# ruka.net
KiCad netlist of a schematic drawn in Altium Designer
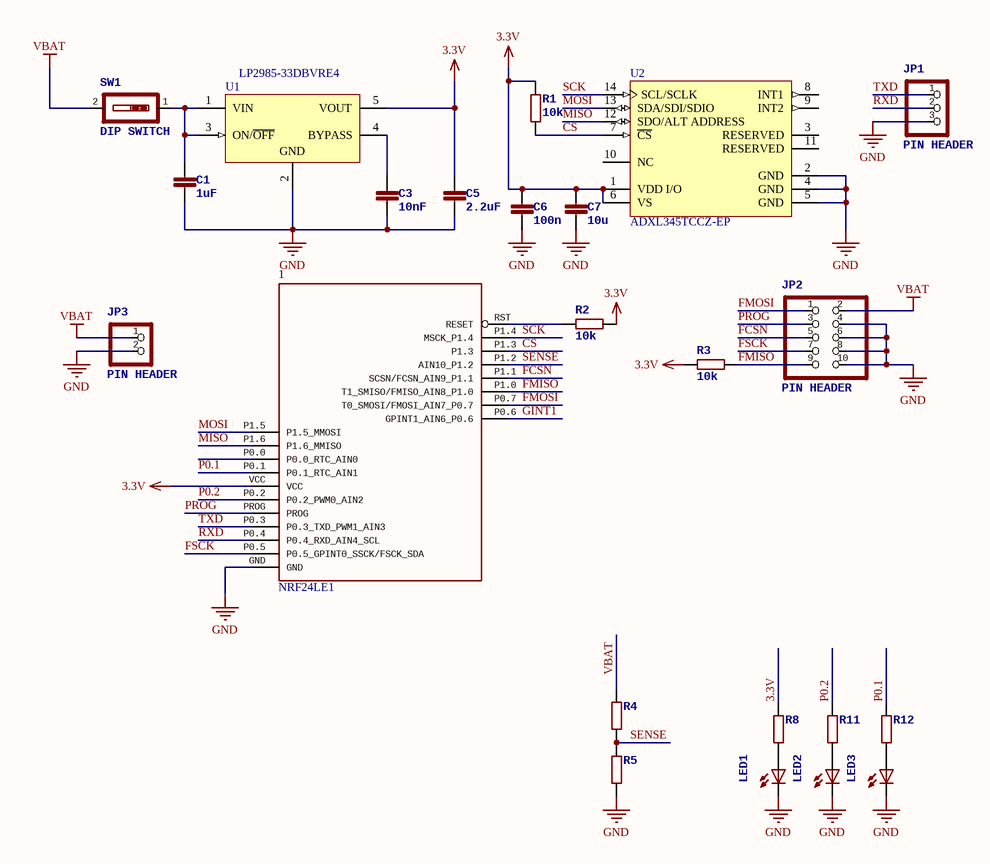
[diagram p0: ruka.SchDoc]

(export (version "E")
  (design (tool "Eeschema 10.0.6"))
  (components
    (comp (ref "1") (value "NRF24LE1") (footprint "SMDNRF") (libsource (lib "nrf24le1") (part "NRF24LE1")))
    (comp (ref "C1") (value "1uF") (footprint "C0805K") (libsource (lib "rcl") (part "C-EUC0805K")))
    (comp (ref "C3") (value "10nF") (footprint "C0805K") (libsource (lib "rcl") (part "C-EUC0805K")))
    (comp (ref "C5") (value "2.2uF") (footprint "C0805K") (libsource (lib "rcl") (part "C-EUC0805K")))
    (comp (ref "C6") (value "100n") (footprint "C0805K") (libsource (lib "rcl") (part "C-EUC0805K")))
    (comp (ref "C7") (value "10u") (footprint "C0805K") (libsource (lib "rcl") (part "C-EUC0805K")))
    (comp (ref "JP1")
      (value "PIN HEADER")
      (footprint "1X03/90")
      (libsource (lib "pinhead") (part "PINHD-1X3/90"))
    )
    (comp (ref "JP2")
      (value "PIN HEADER")
      (footprint "2X05/90")
      (libsource (lib "pinhead") (part "PINHD-2X5/90"))
    )
    (comp (ref "JP3")
      (value "PIN HEADER")
      (footprint "1X02/90")
      (libsource (lib "pinhead") (part "PINHD-1X2/90"))
    )
    (comp (ref "LED1")
      (value "LED   OSRAM: - CHIPLED LG R971, LG N971, LY N971, LG Q971, LY Q971, LO R971, LY R971 LH N974, LH R974 LS Q976, LO")
      (footprint "CHIP-LED0603")
      (libsource (lib "led") (part "LEDCHIP-LED0603"))
    )
    (comp (ref "LED2")
      (value "LED   OSRAM: - CHIPLED LG R971, LG N971, LY N971, LG Q971, LY Q971, LO R971, LY R971 LH N974, LH R974 LS Q976, LO")
      (footprint "CHIP-LED0603")
      (libsource (lib "led") (part "LEDCHIP-LED0603"))
    )
    (comp (ref "LED3")
      (value "LED   OSRAM: - CHIPLED LG R971, LG N971, LY N971, LG Q971, LY Q971, LO R971, LY R971 LH N974, LH R974 LS Q976, LO")
      (footprint "CHIP-LED0603")
      (libsource (lib "led") (part "LEDCHIP-LED0603"))
    )
    (comp (ref "R1") (value "10k") (footprint "R0805") (libsource (lib "rcl") (part "R-EU_R0805")))
    (comp (ref "R2") (value "10k") (footprint "R0805") (libsource (lib "rcl") (part "R-EU_R0805")))
    (comp (ref "R3") (value "10k") (footprint "R0805") (libsource (lib "rcl") (part "R-EU_R0805")))
    (comp (ref "R4") (value "~") (footprint "R0805") (libsource (lib "rcl") (part "R-EU_R0805")))
    (comp (ref "R5") (value "~") (footprint "R0805") (libsource (lib "rcl") (part "R-EU_R0805")))
    (comp (ref "R8") (value "~") (footprint "R0805") (libsource (lib "rcl") (part "R-EU_R0805")))
    (comp (ref "R11") (value "~") (footprint "R0805") (libsource (lib "rcl") (part "R-EU_R0805")))
    (comp (ref "R12") (value "~") (footprint "R0805") (libsource (lib "rcl") (part "R-EU_R0805")))
    (comp (ref "SW1") (value "DIP SWITCH") (footprint "EDG-01") (libsource (lib "special") (part "SW_DIP-1")))
    (comp (ref "U1")
      (value "LP2985-33DBVRE4")
      (footprint "TI-DBV5_V")
      (fields (field (name "MANUFACTURER") "Texas Instruments"))
      (libsource (lib "Altium Content Vault") (part "TI-LP2985_A-10DBV5"))
    )
    (comp (ref "U2")
      (value "ADXL345TCCZ-EP")
      (footprint "ADI-CC-14-1_V")
      (fields (field (name "MANUFACTURER") "Analog Devices"))
      (libsource (lib "Altium Content Vault") (part "ADI-ADXL34X-CC-14-1"))
    )
  )
  (nets
    (net (code "1") (name "/FCSN") (class "Default")
      (node (ref "1") (pin "P1.1") (pinfunction "SCSN/FCSN_AIN9_P1.1_P1.1") (pintype "passive"))
      (node (ref "JP2") (pin "5") (pinfunction "5_5") (pintype "passive"))
    )
    (net (code "2") (name "/FMISO") (class "Default")
      (node (ref "1") (pin "P1.0") (pinfunction "T1_SMISO/FMISO_AIN8_P1.0_P1.0") (pintype "passive"))
      (node (ref "JP2") (pin "9") (pinfunction "9_9") (pintype "passive"))
      (node (ref "R3") (pin "2") (pinfunction "2_2") (pintype "passive"))
    )
    (net (code "3") (name "/FMOSI") (class "Default")
      (node (ref "1") (pin "P0.7") (pinfunction "T0_SMOSI/FMOSI_AIN7_P0.7_P0.7") (pintype "passive"))
      (node (ref "JP2") (pin "1") (pinfunction "1_1") (pintype "passive"))
    )
    (net (code "4") (name "/FSCK") (class "Default")
      (node (ref "1") (pin "P0.5") (pinfunction "P0.5_GPINT0_SSCK/FSCK_SDA_P0.5") (pintype "passive"))
      (node (ref "JP2") (pin "7") (pinfunction "7_7") (pintype "passive"))
    )
    (net (code "5") (name "/GINT1") (class "Default")
      (node (ref "1") (pin "P0.6") (pinfunction "GPINT1_AIN6_P0.6_P0.6") (pintype "passive"))
    )
    (net (code "6") (name "/MISO") (class "Default")
      (node (ref "1") (pin "P1.6") (pinfunction "P1.6_MMISO_P1.6") (pintype "passive"))
      (node (ref "U2") (pin "12") (pinfunction "SDO/ALT_ADDRESS_12") (pintype "bidirectional"))
    )
    (net (code "7") (name "/MOSI") (class "Default")
      (node (ref "1") (pin "P1.5") (pinfunction "P1.5_MMOSI_P1.5") (pintype "passive"))
      (node (ref "U2") (pin "13") (pinfunction "SDA/SDI/SDIO_13") (pintype "bidirectional"))
    )
    (net (code "8") (name "/P0.1") (class "Default")
      (node (ref "1") (pin "P0.1") (pinfunction "P0.1_RTC_AIN1_P0.1") (pintype "passive"))
      (node (ref "R12") (pin "2") (pinfunction "2_2") (pintype "passive"))
    )
    (net (code "9") (name "/P0.2") (class "Default")
      (node (ref "1") (pin "P0.2") (pinfunction "P0.2_PWM0_AIN2_P0.2") (pintype "passive"))
      (node (ref "R11") (pin "2") (pinfunction "2_2") (pintype "passive"))
    )
    (net (code "10") (name "/PROG") (class "Default")
      (node (ref "1") (pin "PROG") (pinfunction "PROG_PROG") (pintype "passive"))
      (node (ref "JP2") (pin "3") (pinfunction "3_3") (pintype "passive"))
    )
    (net (code "11") (name "/RXD") (class "Default")
      (node (ref "1") (pin "P0.4") (pinfunction "P0.4_RXD_AIN4_SCL_P0.4") (pintype "passive"))
      (node (ref "JP1") (pin "2") (pinfunction "2_2") (pintype "passive"))
    )
    (net (code "12") (name "/SCK") (class "Default")
      (node (ref "1") (pin "P1.4") (pinfunction "MSCK_P1.4_P1.4") (pintype "passive"))
      (node (ref "U2") (pin "14") (pinfunction "SCL/SCLK_14") (pintype "input"))
    )
    (net (code "13") (name "/SENSE") (class "Default")
      (node (ref "1") (pin "P1.2") (pinfunction "AIN10_P1.2_P1.2") (pintype "passive"))
      (node (ref "R4") (pin "1") (pinfunction "1_1") (pintype "passive"))
      (node (ref "R5") (pin "2") (pinfunction "2_2") (pintype "passive"))
    )
    (net (code "14") (name "/TXD") (class "Default")
      (node (ref "1") (pin "P0.3") (pinfunction "P0.3_TXD_PWM1_AIN3_P0.3") (pintype "passive"))
      (node (ref "JP1") (pin "1") (pinfunction "1_1") (pintype "passive"))
    )
    (net (code "15") (name "/~{CS}") (class "Default")
      (node (ref "1") (pin "P1.3") (pinfunction "P1.3_P1.3") (pintype "passive"))
      (node (ref "R1") (pin "1") (pinfunction "1_1") (pintype "passive"))
      (node (ref "U2") (pin "7") (pinfunction "~{CS}_7") (pintype "input"))
    )
    (net (code "16") (name "3.3V") (class "Default")
      (node (ref "1") (pin "VCC") (pinfunction "VCC_VCC") (pintype "passive"))
      (node (ref "C5") (pin "1") (pinfunction "1_1") (pintype "passive"))
      (node (ref "C6") (pin "1") (pinfunction "1_1") (pintype "passive"))
      (node (ref "C7") (pin "1") (pinfunction "1_1") (pintype "passive"))
      (node (ref "R1") (pin "2") (pinfunction "2_2") (pintype "passive"))
      (node (ref "R2") (pin "1") (pinfunction "1_1") (pintype "passive"))
      (node (ref "R3") (pin "1") (pinfunction "1_1") (pintype "passive"))
      (node (ref "R8") (pin "2") (pinfunction "2_2") (pintype "passive"))
      (node (ref "U1") (pin "5") (pinfunction "VOUT_5") (pintype "power_in"))
      (node (ref "U2") (pin "1") (pinfunction "VDD_I/O_1") (pintype "power_in"))
      (node (ref "U2") (pin "6") (pinfunction "VS_6") (pintype "power_in"))
    )
    (net (code "17") (name "GND") (class "Default")
      (node (ref "1") (pin "GND") (pinfunction "GND_GND") (pintype "passive"))
      (node (ref "C1") (pin "2") (pinfunction "2_2") (pintype "passive"))
      (node (ref "C3") (pin "2") (pinfunction "2_2") (pintype "passive"))
      (node (ref "C5") (pin "2") (pinfunction "2_2") (pintype "passive"))
      (node (ref "C6") (pin "2") (pinfunction "2_2") (pintype "passive"))
      (node (ref "C7") (pin "2") (pinfunction "2_2") (pintype "passive"))
      (node (ref "JP1") (pin "3") (pinfunction "3_3") (pintype "passive"))
      (node (ref "JP2") (pin "10") (pinfunction "10_10") (pintype "passive"))
      (node (ref "JP2") (pin "4") (pinfunction "4_4") (pintype "passive"))
      (node (ref "JP2") (pin "6") (pinfunction "6_6") (pintype "passive"))
      (node (ref "JP2") (pin "8") (pinfunction "8_8") (pintype "passive"))
      (node (ref "JP3") (pin "2") (pinfunction "2_2") (pintype "passive"))
      (node (ref "LED1") (pin "C") (pinfunction "C_C") (pintype "passive"))
      (node (ref "LED2") (pin "C") (pinfunction "C_C") (pintype "passive"))
      (node (ref "LED3") (pin "C") (pinfunction "C_C") (pintype "passive"))
      (node (ref "R5") (pin "1") (pinfunction "1_1") (pintype "passive"))
      (node (ref "U1") (pin "2") (pinfunction "GND_2") (pintype "power_in"))
      (node (ref "U2") (pin "2") (pinfunction "GND_2") (pintype "power_in"))
      (node (ref "U2") (pin "4") (pinfunction "GND_4") (pintype "power_in"))
      (node (ref "U2") (pin "5") (pinfunction "GND_5") (pintype "power_in"))
    )
    (net (code "18") (name "Net-(1-RESET)") (class "Default")
      (node (ref "1") (pin "RST") (pinfunction "RESET_RST") (pintype "passive"))
      (node (ref "R2") (pin "2") (pinfunction "2_2") (pintype "passive"))
    )
    (net (code "19") (name "Net-(LED1-PadA)") (class "Default")
      (node (ref "LED1") (pin "A") (pinfunction "A_A") (pintype "passive"))
      (node (ref "R8") (pin "1") (pinfunction "1_1") (pintype "passive"))
    )
    (net (code "20") (name "Net-(LED2-PadA)") (class "Default")
      (node (ref "LED2") (pin "A") (pinfunction "A_A") (pintype "passive"))
      (node (ref "R11") (pin "1") (pinfunction "1_1") (pintype "passive"))
    )
    (net (code "21") (name "Net-(LED3-PadA)") (class "Default")
      (node (ref "LED3") (pin "A") (pinfunction "A_A") (pintype "passive"))
      (node (ref "R12") (pin "1") (pinfunction "1_1") (pintype "passive"))
    )
    (net (code "22") (name "Net-(U1-BYPASS)") (class "Default")
      (node (ref "C3") (pin "1") (pinfunction "1_1") (pintype "passive"))
      (node (ref "U1") (pin "4") (pinfunction "BYPASS_4") (pintype "passive"))
    )
    (net (code "23") (name "Net-(U1-ON{slash}~{OFF})") (class "Default")
      (node (ref "C1") (pin "1") (pinfunction "1_1") (pintype "passive"))
      (node (ref "SW1") (pin "1") (pinfunction "1_1") (pintype "passive"))
      (node (ref "U1") (pin "1") (pinfunction "VIN_1") (pintype "power_in"))
      (node (ref "U1") (pin "3") (pinfunction "ON/~{OFF}_3") (pintype "input"))
    )
    (net (code "24") (name "VBAT") (class "Default")
      (node (ref "JP2") (pin "2") (pinfunction "2_2") (pintype "passive"))
      (node (ref "JP3") (pin "1") (pinfunction "1_1") (pintype "passive"))
      (node (ref "R4") (pin "2") (pinfunction "2_2") (pintype "passive"))
      (node (ref "SW1") (pin "2") (pinfunction "2_2") (pintype "passive"))
    )
    (net (code "25") (name "unconnected-(1-P0.0_RTC_AIN0-PadP0.0)") (class "Default")
      (node (ref "1") (pin "P0.0") (pinfunction "P0.0_RTC_AIN0_P0.0") (pintype "passive"))
    )
    (net (code "26") (name "unconnected-(U2-INT1-Pad8)") (class "Default")
      (node (ref "U2") (pin "8") (pinfunction "INT1_8") (pintype "output"))
    )
    (net (code "27") (name "unconnected-(U2-INT2-Pad9)") (class "Default")
      (node (ref "U2") (pin "9") (pinfunction "INT2_9") (pintype "output"))
    )
    (net (code "28") (name "unconnected-(U2-NC-Pad10)") (class "Default")
      (node (ref "U2") (pin "10") (pinfunction "NC_10") (pintype "passive"))
    )
    (net (code "29") (name "unconnected-(U2-RESERVED-Pad3)") (class "Default")
      (node (ref "U2") (pin "3") (pinfunction "RESERVED_3") (pintype "passive"))
    )
    (net (code "30") (name "unconnected-(U2-RESERVED-Pad11)") (class "Default")
      (node (ref "U2") (pin "11") (pinfunction "RESERVED_11") (pintype "passive"))
    )
  )
)
